# BlindController.net
KiCad netlist of a schematic drawn in Altium Designer
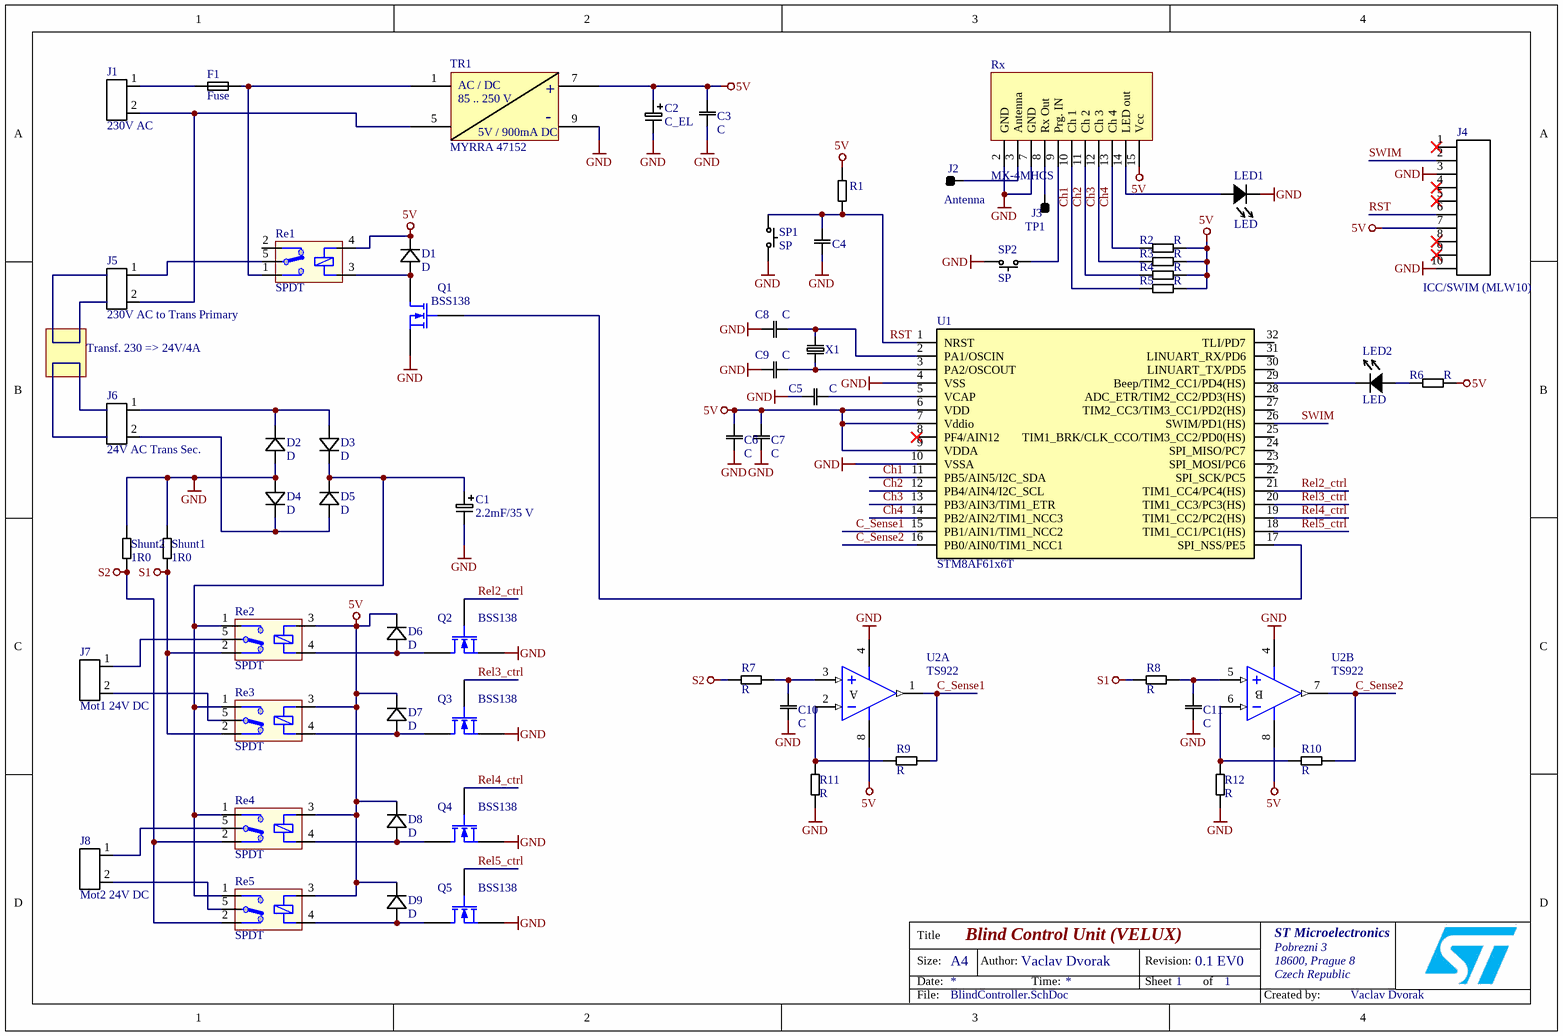
[diagram p0: BlindController.SchDoc]

(export (version "E")
  (design (tool "Eeschema 10.0.6"))
  (components
    (comp (ref "C1")
      (value "2.2mF/35 V")
      (footprint "EL_10X13")
      (libsource (lib "ABU_standard") (part "C_EL_1"))
    )
    (comp (ref "C2") (value "C_EL") (footprint "EL_5x11") (libsource (lib "ABU_standard") (part "C_EL")))
    (comp (ref "C3") (value "C") (footprint "ABU_standard:C0805") (libsource (lib "ABU_standard") (part "C")))
    (comp (ref "C4") (value "~") (footprint "ABU_standard:C0805") (libsource (lib "*") (part "C")))
    (comp (ref "C5") (value "C") (footprint "C0805") (libsource (lib "ABU_standard") (part "C")))
    (comp (ref "C6") (value "C") (footprint "ABU_standard:C0805") (libsource (lib "ABU_standard") (part "C")))
    (comp (ref "C7") (value "C") (footprint "ABU_standard:C0805") (libsource (lib "ABU_standard") (part "C")))
    (comp (ref "C8") (value "C") (footprint "ABU_standard:C0805") (libsource (lib "ABU_STANDARD") (part "C")))
    (comp (ref "C9") (value "C") (footprint "ABU_standard:C0805") (libsource (lib "ABU_STANDARD") (part "C")))
    (comp (ref "C10")
      (value "C")
      (footprint "ABU_standard:C0805")
      (libsource (lib "ABU_standard") (part "C"))
    )
    (comp (ref "C11")
      (value "C")
      (footprint "ABU_standard:C0805")
      (libsource (lib "ABU_standard") (part "C"))
    )
    (comp (ref "D1") (value "D") (footprint "SMA") (libsource (lib "ABU_standard") (part "D")))
    (comp (ref "D2") (value "D") (footprint "DO41") (libsource (lib "ABU_standard") (part "D")))
    (comp (ref "D3") (value "D") (footprint "DO41") (libsource (lib "ABU_standard") (part "D")))
    (comp (ref "D4") (value "D") (footprint "DO41") (libsource (lib "ABU_standard") (part "D")))
    (comp (ref "D5") (value "D") (footprint "DO41") (libsource (lib "ABU_standard") (part "D")))
    (comp (ref "D6") (value "D") (footprint "SMA") (libsource (lib "ABU_standard") (part "D")))
    (comp (ref "D7") (value "D") (footprint "SMA") (libsource (lib "ABU_standard") (part "D")))
    (comp (ref "D8") (value "D") (footprint "SMA") (libsource (lib "ABU_standard") (part "D")))
    (comp (ref "D9") (value "D") (footprint "SMA") (libsource (lib "ABU_standard") (part "D")))
    (comp (ref "F1") (value "Fuse") (footprint "AXIAL-0.5L") (libsource (lib "Private") (part "Fuse")))
    (comp (ref "J1") (value "230V AC") (footprint "ARK_2") (libsource (lib "ABU_standard") (part "CON_2")))
    (comp (ref "J2") (value "Antenna") (footprint "PIN") (libsource (lib "") (part "PIN_1")))
    (comp (ref "J3") (value "TP1") (footprint "PIN") (libsource (lib "ABU_standard") (part "PIN")))
    (comp (ref "J4") (value "ICC/SWIM (MLW10)") (footprint "MLW10") (libsource (lib "*") (part "CON_10")))
    (comp (ref "J5")
      (value "230V AC to Trans Primary")
      (footprint "ARK_2")
      (libsource (lib "ABU_standard") (part "CON_2"))
    )
    (comp (ref "J6")
      (value "24V AC Trans Sec.")
      (footprint "ARK_2")
      (libsource (lib "ABU_standard") (part "CON_2"))
    )
    (comp (ref "J7")
      (value "Mot1 24V DC")
      (footprint "ARK_2")
      (libsource (lib "ABU_standard") (part "CON_2"))
    )
    (comp (ref "J8")
      (value "Mot2 24V DC")
      (footprint "ARK_2")
      (libsource (lib "ABU_standard") (part "CON_2"))
    )
    (comp (ref "LED1") (value "LED") (footprint "LED_SMD") (libsource (lib "ABU_standard") (part "LED")))
    (comp (ref "LED2") (value "LED") (footprint "LED_SMD") (libsource (lib "ABU_standard") (part "LED")))
    (comp (ref "Q1")
      (value "BSS138")
      (footprint "SOT23")
      (description "N-Channel Enhancement Mode Vertical DMOS FET")
      (fields (field (name "PUBLISHER") "Altium Limited"))
      (libsource (lib "ABU_standard") (part "BSS138"))
    )
    (comp (ref "Q2")
      (value "BSS138")
      (footprint "SOT23")
      (description "N-Channel Enhancement Mode Vertical DMOS FET")
      (fields (field (name "PUBLISHER") "Altium Limited"))
      (libsource (lib "ABU_standard") (part "BSS138"))
    )
    (comp (ref "Q3")
      (value "BSS138")
      (footprint "SOT23")
      (description "N-Channel Enhancement Mode Vertical DMOS FET")
      (fields (field (name "PUBLISHER") "Altium Limited"))
      (libsource (lib "ABU_standard") (part "BSS138"))
    )
    (comp (ref "Q4")
      (value "BSS138")
      (footprint "SOT23")
      (description "N-Channel Enhancement Mode Vertical DMOS FET")
      (fields (field (name "PUBLISHER") "Altium Limited"))
      (libsource (lib "ABU_standard") (part "BSS138"))
    )
    (comp (ref "Q5")
      (value "BSS138")
      (footprint "SOT23")
      (description "N-Channel Enhancement Mode Vertical DMOS FET")
      (fields (field (name "PUBLISHER") "Altium Limited"))
      (libsource (lib "ABU_standard") (part "BSS138"))
    )
    (comp (ref "R1") (value "~") (footprint "R0805") (libsource (lib "*") (part "R")))
    (comp (ref "R2") (value "R") (footprint "R0805") (libsource (lib "ABU_standard") (part "R")))
    (comp (ref "R3") (value "R") (footprint "R0805") (libsource (lib "ABU_standard") (part "R")))
    (comp (ref "R4") (value "R") (footprint "R0805") (libsource (lib "ABU_standard") (part "R")))
    (comp (ref "R5") (value "R") (footprint "R0805") (libsource (lib "ABU_standard") (part "R")))
    (comp (ref "R6") (value "R") (footprint "R0805") (libsource (lib "ABU_standard") (part "R")))
    (comp (ref "R7") (value "R") (footprint "R0805") (libsource (lib "") (part "R_2")))
    (comp (ref "R8") (value "R") (footprint "R0805") (libsource (lib "") (part "R_2")))
    (comp (ref "R9") (value "R") (footprint "R0805") (libsource (lib "ABU_standard") (part "R")))
    (comp (ref "R10") (value "R") (footprint "R0805") (libsource (lib "ABU_standard") (part "R")))
    (comp (ref "R11") (value "R") (footprint "R0805") (libsource (lib "") (part "R_1")))
    (comp (ref "R12") (value "R") (footprint "R0805") (libsource (lib "") (part "R_1")))
    (comp (ref "Re1")
      (value "SPDT")
      (footprint "Rele_JS-K")
      (description "rele SPDT")
      (libsource (lib "") (part "Rele_SPDT_1"))
    )
    (comp (ref "Re2")
      (value "SPDT")
      (footprint "Rele_JS-K")
      (description "rele SPDT")
      (libsource (lib "Private") (part "Rele_SPDT"))
    )
    (comp (ref "Re3")
      (value "SPDT")
      (footprint "Rele_JS-K")
      (description "rele SPDT")
      (libsource (lib "Private") (part "Rele_SPDT"))
    )
    (comp (ref "Re4")
      (value "SPDT")
      (footprint "Rele_JS-K")
      (description "rele SPDT")
      (libsource (lib "Private") (part "Rele_SPDT"))
    )
    (comp (ref "Re5")
      (value "SPDT")
      (footprint "Rele_JS-K")
      (description "rele SPDT")
      (libsource (lib "Private") (part "Rele_SPDT"))
    )
    (comp (ref "Rx") (value "MX-4MHCS") (footprint "RX-4MHCS") (libsource (lib "Private") (part "RX-4MHCS")))
    (comp (ref "Shunt1") (value "1R0") (footprint "R Shunt S-2") (libsource (lib "") (part "R_1")))
    (comp (ref "Shunt2") (value "1R0") (footprint "R Shunt S-2") (libsource (lib "") (part "R_1")))
    (comp (ref "SP1") (value "SP") (footprint "DIP_PUSH_BUTTON") (libsource (lib "*") (part "SP")))
    (comp (ref "SP2") (value "SP") (footprint "DIP_PUSH_BUTTON") (libsource (lib "ABU_standard") (part "SP")))
    (comp (ref "TR1")
      (value "MYRRA 47152")
      (footprint "Private:Myrra47000")
      (description "AC/DC  IN:85..260 V AC(DC), OUT: 5V/900mA DC")
      (libsource (lib "Private") (part "MYRRA_AC_DC"))
    )
    (comp (ref "U1")
      (value "STM8AF61x6T")
      (footprint "QFP32")
      (libsource (lib "ABU_standard") (part "STM8AF61x6T"))
    )
    (comp (ref "U2")
      (value "TS922")
      (footprint "SO8_L")
      (description "Rail-to-Rail CMOS Dual Operational Amplifier")
      (fields (field (name "PUBLISHER") "Altium Limited"))
      (libsource (lib "ST Operational Amplifier") (part "TS912ID"))
    )
    (comp (ref "X1") (value "~") (footprint "HC-49U") (libsource (lib "ABU_STANDARD") (part "XTALL")))
  )
  (nets
    (net (code "1") (name "/C_Sense1") (class "Default")
      (node (ref "R9") (pin "1") (pinfunction "1_1") (pintype "passive"))
      (node (ref "U1") (pin "15") (pinfunction "PB1/AIN1/TIM1_NCC2_15") (pintype "passive"))
      (node (ref "U2") (pin "1") (pinfunction "OUT_1") (pintype "output"))
    )
    (net (code "2") (name "/C_Sense2") (class "Default")
      (node (ref "R10") (pin "1") (pinfunction "1_1") (pintype "passive"))
      (node (ref "U1") (pin "16") (pinfunction "PB0/AIN0/TIM1_NCC1_16") (pintype "passive"))
      (node (ref "U2") (pin "7") (pinfunction "OUT_7") (pintype "output"))
    )
    (net (code "3") (name "/Ch1") (class "Default")
      (node (ref "R5") (pin "2") (pinfunction "2_2") (pintype "passive"))
      (node (ref "Rx") (pin "10") (pinfunction "Ch_1_10") (pintype "passive"))
      (node (ref "U1") (pin "11") (pinfunction "PB5/AIN5/I2C_SDA_11") (pintype "passive"))
    )
    (net (code "4") (name "/Ch2") (class "Default")
      (node (ref "R4") (pin "2") (pinfunction "2_2") (pintype "passive"))
      (node (ref "Rx") (pin "11") (pinfunction "Ch_2_11") (pintype "passive"))
      (node (ref "U1") (pin "12") (pinfunction "PB4/AIN4/I2C_SCL_12") (pintype "passive"))
    )
    (net (code "5") (name "/Ch3") (class "Default")
      (node (ref "R3") (pin "2") (pinfunction "2_2") (pintype "passive"))
      (node (ref "Rx") (pin "12") (pinfunction "Ch_3_12") (pintype "passive"))
      (node (ref "U1") (pin "13") (pinfunction "PB3/AIN3/TIM1_ETR_13") (pintype "passive"))
    )
    (net (code "6") (name "/Ch4") (class "Default")
      (node (ref "R2") (pin "2") (pinfunction "2_2") (pintype "passive"))
      (node (ref "Rx") (pin "13") (pinfunction "Ch_4_13") (pintype "passive"))
      (node (ref "U1") (pin "14") (pinfunction "PB2/AIN2/TIM1_NCC3_14") (pintype "passive"))
    )
    (net (code "7") (name "/RST") (class "Default")
      (node (ref "C4") (pin "2") (pinfunction "2_2") (pintype "passive"))
      (node (ref "J4") (pin "6") (pinfunction "6_6") (pintype "passive"))
      (node (ref "R1") (pin "2") (pinfunction "2_2") (pintype "passive"))
      (node (ref "SP1") (pin "1") (pinfunction "1_1") (pintype "passive"))
      (node (ref "U1") (pin "1") (pinfunction "NRST_1") (pintype "passive"))
    )
    (net (code "8") (name "/Rel2_ctrl") (class "Default")
      (node (ref "Q2") (pin "1") (pinfunction "G_1") (pintype "passive"))
      (node (ref "U1") (pin "21") (pinfunction "TIM1_CC4/PC4(HS)_21") (pintype "passive"))
    )
    (net (code "9") (name "/Rel3_ctrl") (class "Default")
      (node (ref "Q3") (pin "1") (pinfunction "G_1") (pintype "passive"))
      (node (ref "U1") (pin "20") (pinfunction "TIM1_CC3/PC3(HS)_20") (pintype "passive"))
    )
    (net (code "10") (name "/Rel4_ctrl") (class "Default")
      (node (ref "Q4") (pin "1") (pinfunction "G_1") (pintype "passive"))
      (node (ref "U1") (pin "19") (pinfunction "TIM1_CC2/PC2(HS)_19") (pintype "passive"))
    )
    (net (code "11") (name "/Rel5_ctrl") (class "Default")
      (node (ref "Q5") (pin "1") (pinfunction "G_1") (pintype "passive"))
      (node (ref "U1") (pin "18") (pinfunction "TIM1_CC1/PC1(HS)_18") (pintype "passive"))
    )
    (net (code "12") (name "/SWIM") (class "Default")
      (node (ref "J4") (pin "2") (pinfunction "2_2") (pintype "passive"))
      (node (ref "U1") (pin "26") (pinfunction "SWIM/PD1(HS)_26") (pintype "passive"))
    )
    (net (code "13") (name "5V") (class "Default")
      (node (ref "C2") (pin "1") (pinfunction "1_1") (pintype "passive"))
      (node (ref "C3") (pin "2") (pinfunction "2_2") (pintype "passive"))
      (node (ref "C6") (pin "2") (pinfunction "2_2") (pintype "passive"))
      (node (ref "C7") (pin "2") (pinfunction "2_2") (pintype "passive"))
      (node (ref "D1") (pin "2") (pinfunction "K_2") (pintype "passive"))
      (node (ref "D6") (pin "2") (pinfunction "K_2") (pintype "passive"))
      (node (ref "D7") (pin "2") (pinfunction "K_2") (pintype "passive"))
      (node (ref "D8") (pin "2") (pinfunction "K_2") (pintype "passive"))
      (node (ref "D9") (pin "2") (pinfunction "K_2") (pintype "passive"))
      (node (ref "J4") (pin "7") (pinfunction "7_7") (pintype "passive"))
      (node (ref "R1") (pin "1") (pinfunction "1_1") (pintype "passive"))
      (node (ref "R2") (pin "1") (pinfunction "1_1") (pintype "passive"))
      (node (ref "R3") (pin "1") (pinfunction "1_1") (pintype "passive"))
      (node (ref "R4") (pin "1") (pinfunction "1_1") (pintype "passive"))
      (node (ref "R5") (pin "1") (pinfunction "1_1") (pintype "passive"))
      (node (ref "R6") (pin "1") (pinfunction "1_1") (pintype "passive"))
      (node (ref "Re1") (pin "4") (pinfunction "4_4") (pintype "passive"))
      (node (ref "Re2") (pin "3") (pinfunction "3_3") (pintype "passive"))
      (node (ref "Re3") (pin "3") (pinfunction "3_3") (pintype "passive"))
      (node (ref "Re4") (pin "3") (pinfunction "3_3") (pintype "passive"))
      (node (ref "Re5") (pin "3") (pinfunction "3_3") (pintype "passive"))
      (node (ref "Rx") (pin "15") (pinfunction "Vcc_15") (pintype "passive"))
      (node (ref "TR1") (pin "7") (pinfunction "7_7") (pintype "passive"))
      (node (ref "U1") (pin "6") (pinfunction "VDD_6") (pintype "passive"))
      (node (ref "U1") (pin "7") (pinfunction "Vddio_7") (pintype "passive"))
      (node (ref "U1") (pin "9") (pinfunction "VDDA_9") (pintype "passive"))
      (node (ref "U2") (pin "8") (pinfunction "V+_8") (pintype "power_in"))
    )
    (net (code "14") (name "GND") (class "Default")
      (node (ref "C1") (pin "2") (pinfunction "2_2") (pintype "passive"))
      (node (ref "C10") (pin "1") (pinfunction "1_1") (pintype "passive"))
      (node (ref "C11") (pin "1") (pinfunction "1_1") (pintype "passive"))
      (node (ref "C2") (pin "2") (pinfunction "2_2") (pintype "passive"))
      (node (ref "C3") (pin "1") (pinfunction "1_1") (pintype "passive"))
      (node (ref "C4") (pin "1") (pinfunction "1_1") (pintype "passive"))
      (node (ref "C5") (pin "1") (pinfunction "1_1") (pintype "passive"))
      (node (ref "C6") (pin "1") (pinfunction "1_1") (pintype "passive"))
      (node (ref "C7") (pin "1") (pinfunction "1_1") (pintype "passive"))
      (node (ref "C8") (pin "1") (pinfunction "1_1") (pintype "passive"))
      (node (ref "C9") (pin "1") (pinfunction "1_1") (pintype "passive"))
      (node (ref "D2") (pin "1") (pinfunction "A_1") (pintype "passive"))
      (node (ref "D4") (pin "1") (pinfunction "A_1") (pintype "passive"))
      (node (ref "J4") (pin "10") (pinfunction "10_10") (pintype "passive"))
      (node (ref "J4") (pin "3") (pinfunction "3_3") (pintype "passive"))
      (node (ref "LED1") (pin "2") (pinfunction "K_2") (pintype "passive"))
      (node (ref "Q1") (pin "2") (pinfunction "S_2") (pintype "passive"))
      (node (ref "Q2") (pin "2") (pinfunction "S_2") (pintype "passive"))
      (node (ref "Q3") (pin "2") (pinfunction "S_2") (pintype "passive"))
      (node (ref "Q4") (pin "2") (pinfunction "S_2") (pintype "passive"))
      (node (ref "Q5") (pin "2") (pinfunction "S_2") (pintype "passive"))
      (node (ref "R11") (pin "2") (pinfunction "2_2") (pintype "passive"))
      (node (ref "R12") (pin "2") (pinfunction "2_2") (pintype "passive"))
      (node (ref "Rx") (pin "2") (pinfunction "GND_2") (pintype "passive"))
      (node (ref "Rx") (pin "7") (pinfunction "GND_7") (pintype "passive"))
      (node (ref "SP1") (pin "2") (pinfunction "2_2") (pintype "passive"))
      (node (ref "SP2") (pin "2") (pinfunction "2_2") (pintype "passive"))
      (node (ref "Shunt1") (pin "1") (pinfunction "1_1") (pintype "passive"))
      (node (ref "Shunt2") (pin "1") (pinfunction "1_1") (pintype "passive"))
      (node (ref "TR1") (pin "9") (pinfunction "9_9") (pintype "passive"))
      (node (ref "U1") (pin "10") (pinfunction "VSSA_10") (pintype "passive"))
      (node (ref "U1") (pin "4") (pinfunction "VSS_4") (pintype "passive"))
      (node (ref "U2") (pin "4") (pinfunction "V-_4") (pintype "power_in"))
    )
    (net (code "15") (name "Net-(D1-A)") (class "Default")
      (node (ref "D1") (pin "1") (pinfunction "A_1") (pintype "passive"))
      (node (ref "Q1") (pin "3") (pinfunction "D_3") (pintype "passive"))
      (node (ref "Re1") (pin "3") (pinfunction "3_3") (pintype "passive"))
    )
    (net (code "16") (name "Net-(D2-K)") (class "Default")
      (node (ref "D2") (pin "2") (pinfunction "K_2") (pintype "passive"))
      (node (ref "D3") (pin "1") (pinfunction "A_1") (pintype "passive"))
      (node (ref "J6") (pin "1") (pinfunction "1_1") (pintype "passive"))
    )
    (net (code "17") (name "Net-(D3-K)") (class "Default")
      (node (ref "C1") (pin "1") (pinfunction "1_1") (pintype "passive"))
      (node (ref "D3") (pin "2") (pinfunction "K_2") (pintype "passive"))
      (node (ref "D5") (pin "2") (pinfunction "K_2") (pintype "passive"))
      (node (ref "Re2") (pin "1") (pinfunction "1_1") (pintype "passive"))
      (node (ref "Re3") (pin "1") (pinfunction "1_1") (pintype "passive"))
      (node (ref "Re4") (pin "1") (pinfunction "1_1") (pintype "passive"))
      (node (ref "Re5") (pin "1") (pinfunction "1_1") (pintype "passive"))
    )
    (net (code "18") (name "Net-(D4-K)") (class "Default")
      (node (ref "D4") (pin "2") (pinfunction "K_2") (pintype "passive"))
      (node (ref "D5") (pin "1") (pinfunction "A_1") (pintype "passive"))
      (node (ref "J6") (pin "2") (pinfunction "2_2") (pintype "passive"))
    )
    (net (code "19") (name "Net-(D6-A)") (class "Default")
      (node (ref "D6") (pin "1") (pinfunction "A_1") (pintype "passive"))
      (node (ref "Q2") (pin "3") (pinfunction "D_3") (pintype "passive"))
      (node (ref "Re2") (pin "4") (pinfunction "4_4") (pintype "passive"))
    )
    (net (code "20") (name "Net-(D7-A)") (class "Default")
      (node (ref "D7") (pin "1") (pinfunction "A_1") (pintype "passive"))
      (node (ref "Q3") (pin "3") (pinfunction "D_3") (pintype "passive"))
      (node (ref "Re3") (pin "4") (pinfunction "4_4") (pintype "passive"))
    )
    (net (code "21") (name "Net-(D8-A)") (class "Default")
      (node (ref "D8") (pin "1") (pinfunction "A_1") (pintype "passive"))
      (node (ref "Q4") (pin "3") (pinfunction "D_3") (pintype "passive"))
      (node (ref "Re4") (pin "4") (pinfunction "4_4") (pintype "passive"))
    )
    (net (code "22") (name "Net-(D9-A)") (class "Default")
      (node (ref "D9") (pin "1") (pinfunction "A_1") (pintype "passive"))
      (node (ref "Q5") (pin "3") (pinfunction "D_3") (pintype "passive"))
      (node (ref "Re5") (pin "4") (pinfunction "4_4") (pintype "passive"))
    )
    (net (code "23") (name "Net-(F1-Pad1)") (class "Default")
      (node (ref "F1") (pin "1") (pinfunction "1_1") (pintype "passive"))
      (node (ref "Re1") (pin "1") (pinfunction "1_1") (pintype "passive"))
      (node (ref "TR1") (pin "1") (pinfunction "1_1") (pintype "passive"))
    )
    (net (code "24") (name "Net-(F1-Pad2)") (class "Default")
      (node (ref "F1") (pin "2") (pinfunction "2_2") (pintype "passive"))
      (node (ref "J1") (pin "1") (pinfunction "1_1") (pintype "passive"))
    )
    (net (code "25") (name "Net-(J1-Pad2)") (class "Default")
      (node (ref "J1") (pin "2") (pinfunction "2_2") (pintype "passive"))
      (node (ref "J5") (pin "2") (pinfunction "2_2") (pintype "passive"))
      (node (ref "TR1") (pin "5") (pinfunction "5_5") (pintype "passive"))
    )
    (net (code "26") (name "Net-(J5-Pad1)") (class "Default")
      (node (ref "J5") (pin "1") (pinfunction "1_1") (pintype "passive"))
      (node (ref "Re1") (pin "5") (pinfunction "5_5") (pintype "passive"))
    )
    (net (code "27") (name "Net-(J7-Pad1)") (class "Default")
      (node (ref "J7") (pin "1") (pinfunction "1_1") (pintype "passive"))
      (node (ref "Re2") (pin "5") (pinfunction "5_5") (pintype "passive"))
    )
    (net (code "28") (name "Net-(J7-Pad2)") (class "Default")
      (node (ref "J7") (pin "2") (pinfunction "2_2") (pintype "passive"))
      (node (ref "Re3") (pin "5") (pinfunction "5_5") (pintype "passive"))
    )
    (net (code "29") (name "Net-(J8-Pad1)") (class "Default")
      (node (ref "J8") (pin "1") (pinfunction "1_1") (pintype "passive"))
      (node (ref "Re4") (pin "5") (pinfunction "5_5") (pintype "passive"))
    )
    (net (code "30") (name "Net-(J8-Pad2)") (class "Default")
      (node (ref "J8") (pin "2") (pinfunction "2_2") (pintype "passive"))
      (node (ref "Re5") (pin "5") (pinfunction "5_5") (pintype "passive"))
    )
    (net (code "31") (name "Net-(LED1-A)") (class "Default")
      (node (ref "LED1") (pin "1") (pinfunction "A_1") (pintype "passive"))
      (node (ref "Rx") (pin "14") (pinfunction "LED_out_14") (pintype "passive"))
    )
    (net (code "32") (name "Net-(LED2-A)") (class "Default")
      (node (ref "LED2") (pin "1") (pinfunction "A_1") (pintype "passive"))
      (node (ref "R6") (pin "2") (pinfunction "2_2") (pintype "passive"))
    )
    (net (code "33") (name "Net-(LED2-K)") (class "Default")
      (node (ref "LED2") (pin "2") (pinfunction "K_2") (pintype "passive"))
      (node (ref "U1") (pin "29") (pinfunction "Beep/TIM2_CC1/PD4(HS)_29") (pintype "passive"))
    )
    (net (code "34") (name "Net-(Q1-G)") (class "Default")
      (node (ref "Q1") (pin "1") (pinfunction "G_1") (pintype "passive"))
      (node (ref "U1") (pin "17") (pinfunction "SPI_NSS/PE5_17") (pintype "passive"))
    )
    (net (code "35") (name "Net-(Rx-Antenna)") (class "Default")
      (node (ref "J2") (pin "1") (pinfunction "1_1") (pintype "passive"))
      (node (ref "Rx") (pin "3") (pinfunction "Antenna_3") (pintype "passive"))
    )
    (net (code "36") (name "Net-(Rx-Prg._IN)") (class "Default")
      (node (ref "Rx") (pin "9") (pinfunction "Prg._IN_9") (pintype "passive"))
      (node (ref "SP2") (pin "1") (pinfunction "1_1") (pintype "passive"))
    )
    (net (code "37") (name "Net-(Rx-Rx_Out)") (class "Default")
      (node (ref "J3") (pin "1") (pinfunction "1_1") (pintype "passive"))
      (node (ref "Rx") (pin "8") (pinfunction "Rx_Out_8") (pintype "passive"))
    )
    (net (code "38") (name "Net-(U1-PA1{slash}OSCIN)") (class "Default")
      (node (ref "C8") (pin "2") (pinfunction "2_2") (pintype "passive"))
      (node (ref "U1") (pin "2") (pinfunction "PA1/OSCIN_2") (pintype "passive"))
      (node (ref "X1") (pin "1") (pinfunction "1_1") (pintype "passive"))
    )
    (net (code "39") (name "Net-(U1-PA2{slash}OSCOUT)") (class "Default")
      (node (ref "C9") (pin "2") (pinfunction "2_2") (pintype "passive"))
      (node (ref "U1") (pin "3") (pinfunction "PA2/OSCOUT_3") (pintype "passive"))
      (node (ref "X1") (pin "2") (pinfunction "2_2") (pintype "passive"))
    )
    (net (code "40") (name "Net-(U1-VCAP)") (class "Default")
      (node (ref "C5") (pin "2") (pinfunction "2_2") (pintype "passive"))
      (node (ref "U1") (pin "5") (pinfunction "VCAP_5") (pintype "passive"))
    )
    (net (code "41") (name "Net-(U2A-IN+)") (class "Default")
      (node (ref "C10") (pin "2") (pinfunction "2_2") (pintype "passive"))
      (node (ref "R7") (pin "2") (pinfunction "2_2") (pintype "passive"))
      (node (ref "U2") (pin "3") (pinfunction "IN+_3") (pintype "input"))
    )
    (net (code "42") (name "Net-(U2A-IN-)") (class "Default")
      (node (ref "R11") (pin "1") (pinfunction "1_1") (pintype "passive"))
      (node (ref "R9") (pin "2") (pinfunction "2_2") (pintype "passive"))
      (node (ref "U2") (pin "2") (pinfunction "IN-_2") (pintype "input"))
    )
    (net (code "43") (name "Net-(U2B-IN+)") (class "Default")
      (node (ref "C11") (pin "2") (pinfunction "2_2") (pintype "passive"))
      (node (ref "R8") (pin "2") (pinfunction "2_2") (pintype "passive"))
      (node (ref "U2") (pin "5") (pinfunction "IN+_5") (pintype "input"))
    )
    (net (code "44") (name "Net-(U2B-IN-)") (class "Default")
      (node (ref "R10") (pin "2") (pinfunction "2_2") (pintype "passive"))
      (node (ref "R12") (pin "1") (pinfunction "1_1") (pintype "passive"))
      (node (ref "U2") (pin "6") (pinfunction "IN-_6") (pintype "input"))
    )
    (net (code "45") (name "S1") (class "Default")
      (node (ref "R8") (pin "1") (pinfunction "1_1") (pintype "passive"))
      (node (ref "Re2") (pin "2") (pinfunction "2_2") (pintype "passive"))
      (node (ref "Re3") (pin "2") (pinfunction "2_2") (pintype "passive"))
      (node (ref "Shunt1") (pin "2") (pinfunction "2_2") (pintype "passive"))
    )
    (net (code "46") (name "S2") (class "Default")
      (node (ref "R7") (pin "1") (pinfunction "1_1") (pintype "passive"))
      (node (ref "Re4") (pin "2") (pinfunction "2_2") (pintype "passive"))
      (node (ref "Re5") (pin "2") (pinfunction "2_2") (pintype "passive"))
      (node (ref "Shunt2") (pin "2") (pinfunction "2_2") (pintype "passive"))
    )
    (net (code "47") (name "unconnected-(J4-Pad1)") (class "Default")
      (node (ref "J4") (pin "1") (pinfunction "1_1") (pintype "passive+no_connect"))
    )
    (net (code "48") (name "unconnected-(J4-Pad4)") (class "Default")
      (node (ref "J4") (pin "4") (pinfunction "4_4") (pintype "passive+no_connect"))
    )
    (net (code "49") (name "unconnected-(J4-Pad5)") (class "Default")
      (node (ref "J4") (pin "5") (pinfunction "5_5") (pintype "passive+no_connect"))
    )
    (net (code "50") (name "unconnected-(J4-Pad8)") (class "Default")
      (node (ref "J4") (pin "8") (pinfunction "8_8") (pintype "passive+no_connect"))
    )
    (net (code "51") (name "unconnected-(J4-Pad9)") (class "Default")
      (node (ref "J4") (pin "9") (pinfunction "9_9") (pintype "passive+no_connect"))
    )
    (net (code "52") (name "unconnected-(Re1-Pad2)") (class "Default")
      (node (ref "Re1") (pin "2") (pinfunction "2_2") (pintype "passive"))
    )
    (net (code "53") (name "unconnected-(U1-ADC_ETR{slash}TIM2_CC2{slash}PD3(HS)-Pad28)") (class "Default")
      (node (ref "U1") (pin "28") (pinfunction "ADC_ETR/TIM2_CC2/PD3(HS)_28") (pintype "passive"))
    )
    (net (code "54") (name "unconnected-(U1-LINUART_RX{slash}PD6-Pad31)") (class "Default")
      (node (ref "U1") (pin "31") (pinfunction "LINUART_RX/PD6_31") (pintype "passive"))
    )
    (net (code "55") (name "unconnected-(U1-LINUART_TX{slash}PD5-Pad30)") (class "Default")
      (node (ref "U1") (pin "30") (pinfunction "LINUART_TX/PD5_30") (pintype "passive"))
    )
    (net (code "56") (name "unconnected-(U1-PF4{slash}AIN12-Pad8)") (class "Default")
      (node (ref "U1") (pin "8") (pinfunction "PF4/AIN12_8") (pintype "passive+no_connect"))
    )
    (net (code "57") (name "unconnected-(U1-SPI_MISO{slash}PC7-Pad24)") (class "Default")
      (node (ref "U1") (pin "24") (pinfunction "SPI_MISO/PC7_24") (pintype "passive"))
    )
    (net (code "58") (name "unconnected-(U1-SPI_MOSI{slash}PC6-Pad23)") (class "Default")
      (node (ref "U1") (pin "23") (pinfunction "SPI_MOSI/PC6_23") (pintype "passive"))
    )
    (net (code "59") (name "unconnected-(U1-SPI_SCK{slash}PC5-Pad22)") (class "Default")
      (node (ref "U1") (pin "22") (pinfunction "SPI_SCK/PC5_22") (pintype "passive"))
    )
    (net (code "60") (name "unconnected-(U1-TIM1_BRK{slash}CLK_CCO{slash}TIM3_CC2{slash}PD0(HS)-Pad25)") (class "Default")
      (node (ref "U1") (pin "25") (pinfunction "TIM1_BRK/CLK_CCO/TIM3_CC2/PD0(HS)_25") (pintype "passive"))
    )
    (net (code "61") (name "unconnected-(U1-TIM2_CC3{slash}TIM3_CC1{slash}PD2(HS)-Pad27)") (class "Default")
      (node (ref "U1") (pin "27") (pinfunction "TIM2_CC3/TIM3_CC1/PD2(HS)_27") (pintype "passive"))
    )
    (net (code "62") (name "unconnected-(U1-TLI{slash}PD7-Pad32)") (class "Default")
      (node (ref "U1") (pin "32") (pinfunction "TLI/PD7_32") (pintype "passive"))
    )
  )
)
